# NumPad.net
KiCad netlist of a schematic drawn in EAGLE
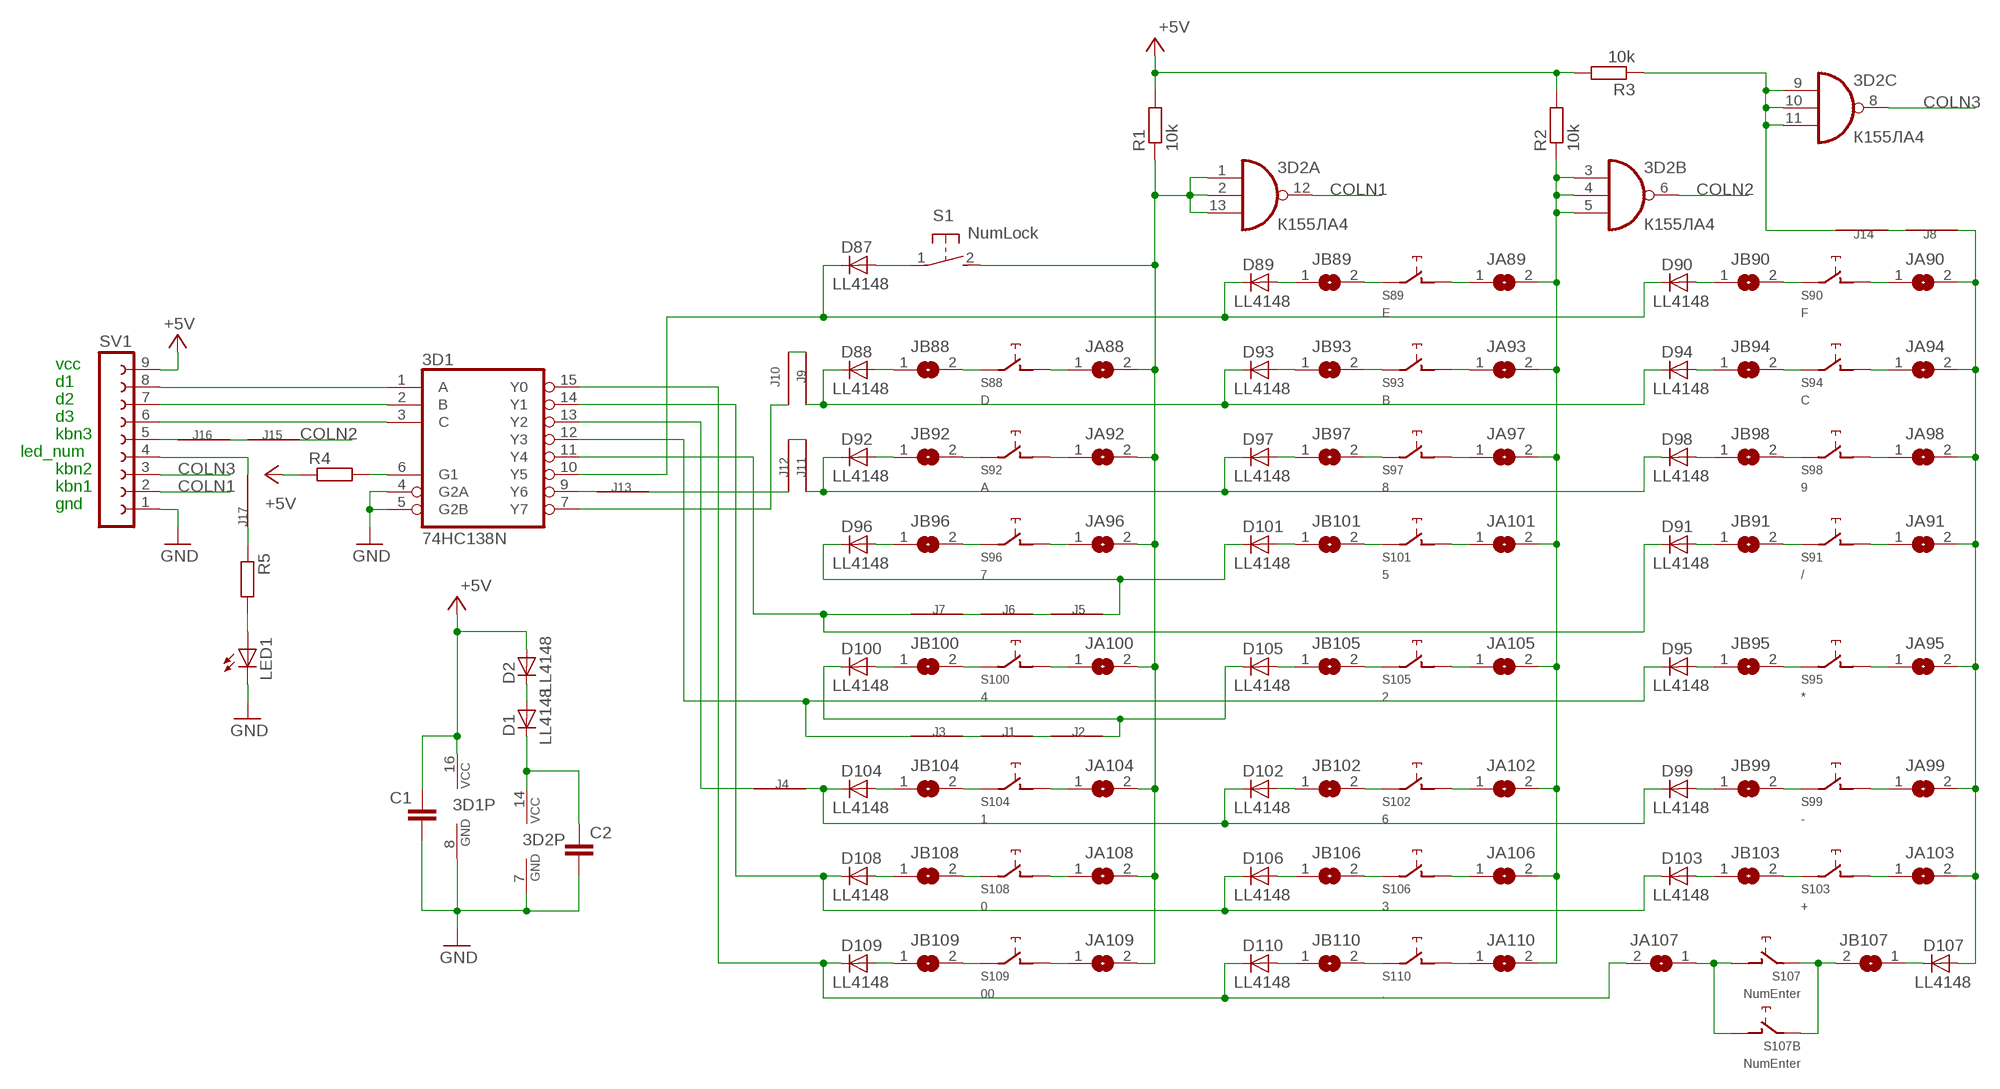
[diagram p0: schematic, sheet 1]

(export (version "E")
  (design (tool "Eeschema 10.0.6"))
  (components
    (comp (ref "3D1")
      (value "74HC138N")
      (footprint "eagle-import:DIL16")
      (libsource (lib "eagle-import") (part "74138NHC"))
    )
    (comp (ref "3D2")
      (value "К155ЛА4")
      (footprint "eagle-import:DIL14")
      (libsource (lib "eagle-import") (part "7410NHC"))
    )
    (comp (ref "C1")
      (value "C-EUC1206")
      (footprint "eagle-import:C1206")
      (libsource (lib "eagle-import") (part "C-EUC1206"))
    )
    (comp (ref "C2")
      (value "C-EUC1206")
      (footprint "eagle-import:C1206")
      (libsource (lib "eagle-import") (part "C-EUC1206"))
    )
    (comp (ref "D1")
      (value "LL4148")
      (footprint "eagle-import:SOD80C")
      (libsource (lib "eagle-import") (part "LL4148"))
    )
    (comp (ref "D2")
      (value "LL4148")
      (footprint "eagle-import:SOD80C")
      (libsource (lib "eagle-import") (part "LL4148"))
    )
    (comp (ref "D87")
      (value "LL4148")
      (footprint "eagle-import:SOD80C")
      (libsource (lib "eagle-import") (part "LL4148"))
    )
    (comp (ref "D88")
      (value "LL4148")
      (footprint "eagle-import:SOD80C")
      (libsource (lib "eagle-import") (part "LL4148"))
    )
    (comp (ref "D89")
      (value "LL4148")
      (footprint "eagle-import:SOD80C")
      (libsource (lib "eagle-import") (part "LL4148"))
    )
    (comp (ref "D90")
      (value "LL4148")
      (footprint "eagle-import:SOD80C")
      (libsource (lib "eagle-import") (part "LL4148"))
    )
    (comp (ref "D91")
      (value "LL4148")
      (footprint "eagle-import:SOD80C")
      (libsource (lib "eagle-import") (part "LL4148"))
    )
    (comp (ref "D92")
      (value "LL4148")
      (footprint "eagle-import:SOD80C")
      (libsource (lib "eagle-import") (part "LL4148"))
    )
    (comp (ref "D93")
      (value "LL4148")
      (footprint "eagle-import:SOD80C")
      (libsource (lib "eagle-import") (part "LL4148"))
    )
    (comp (ref "D94")
      (value "LL4148")
      (footprint "eagle-import:SOD80C")
      (libsource (lib "eagle-import") (part "LL4148"))
    )
    (comp (ref "D95")
      (value "LL4148")
      (footprint "eagle-import:SOD80C")
      (libsource (lib "eagle-import") (part "LL4148"))
    )
    (comp (ref "D96")
      (value "LL4148")
      (footprint "eagle-import:SOD80C")
      (libsource (lib "eagle-import") (part "LL4148"))
    )
    (comp (ref "D97")
      (value "LL4148")
      (footprint "eagle-import:SOD80C")
      (libsource (lib "eagle-import") (part "LL4148"))
    )
    (comp (ref "D98")
      (value "LL4148")
      (footprint "eagle-import:SOD80C")
      (libsource (lib "eagle-import") (part "LL4148"))
    )
    (comp (ref "D99")
      (value "LL4148")
      (footprint "eagle-import:SOD80C")
      (libsource (lib "eagle-import") (part "LL4148"))
    )
    (comp (ref "D100")
      (value "LL4148")
      (footprint "eagle-import:SOD80C")
      (libsource (lib "eagle-import") (part "LL4148"))
    )
    (comp (ref "D101")
      (value "LL4148")
      (footprint "eagle-import:SOD80C")
      (libsource (lib "eagle-import") (part "LL4148"))
    )
    (comp (ref "D102")
      (value "LL4148")
      (footprint "eagle-import:SOD80C")
      (libsource (lib "eagle-import") (part "LL4148"))
    )
    (comp (ref "D103")
      (value "LL4148")
      (footprint "eagle-import:SOD80C")
      (libsource (lib "eagle-import") (part "LL4148"))
    )
    (comp (ref "D104")
      (value "LL4148")
      (footprint "eagle-import:SOD80C")
      (libsource (lib "eagle-import") (part "LL4148"))
    )
    (comp (ref "D105")
      (value "LL4148")
      (footprint "eagle-import:SOD80C")
      (libsource (lib "eagle-import") (part "LL4148"))
    )
    (comp (ref "D106")
      (value "LL4148")
      (footprint "eagle-import:SOD80C")
      (libsource (lib "eagle-import") (part "LL4148"))
    )
    (comp (ref "D107")
      (value "LL4148")
      (footprint "eagle-import:SOD80C")
      (libsource (lib "eagle-import") (part "LL4148"))
    )
    (comp (ref "D108")
      (value "LL4148")
      (footprint "eagle-import:SOD80C")
      (libsource (lib "eagle-import") (part "LL4148"))
    )
    (comp (ref "D109")
      (value "LL4148")
      (footprint "eagle-import:SOD80C")
      (libsource (lib "eagle-import") (part "LL4148"))
    )
    (comp (ref "D110")
      (value "LL4148")
      (footprint "eagle-import:SOD80C")
      (libsource (lib "eagle-import") (part "LL4148"))
    )
    (comp (ref "J1")
      (value "J")
      (footprint "eagle-import:R1206W")
      (libsource (lib "eagle-import") (part "J"))
    )
    (comp (ref "J2")
      (value "J")
      (footprint "eagle-import:R1206W")
      (libsource (lib "eagle-import") (part "J"))
    )
    (comp (ref "J3")
      (value "J")
      (footprint "eagle-import:R1206W")
      (libsource (lib "eagle-import") (part "J"))
    )
    (comp (ref "J4")
      (value "J")
      (footprint "eagle-import:R1206W")
      (libsource (lib "eagle-import") (part "J"))
    )
    (comp (ref "J5")
      (value "J")
      (footprint "eagle-import:R1206W")
      (libsource (lib "eagle-import") (part "J"))
    )
    (comp (ref "J6")
      (value "J")
      (footprint "eagle-import:R1206W")
      (libsource (lib "eagle-import") (part "J"))
    )
    (comp (ref "J7")
      (value "J")
      (footprint "eagle-import:R1206W")
      (libsource (lib "eagle-import") (part "J"))
    )
    (comp (ref "J8")
      (value "J")
      (footprint "eagle-import:R1206W")
      (libsource (lib "eagle-import") (part "J"))
    )
    (comp (ref "J9")
      (value "J")
      (footprint "eagle-import:R1206W")
      (libsource (lib "eagle-import") (part "J"))
    )
    (comp (ref "J10")
      (value "J")
      (footprint "eagle-import:R1206W")
      (libsource (lib "eagle-import") (part "J"))
    )
    (comp (ref "J11")
      (value "J")
      (footprint "eagle-import:R1206W")
      (libsource (lib "eagle-import") (part "J"))
    )
    (comp (ref "J12")
      (value "J")
      (footprint "eagle-import:R1206W")
      (libsource (lib "eagle-import") (part "J"))
    )
    (comp (ref "J13")
      (value "J")
      (footprint "eagle-import:R1206W")
      (libsource (lib "eagle-import") (part "J"))
    )
    (comp (ref "J14")
      (value "J")
      (footprint "eagle-import:R1206W")
      (libsource (lib "eagle-import") (part "J"))
    )
    (comp (ref "J15")
      (value "J")
      (footprint "eagle-import:R1206W")
      (libsource (lib "eagle-import") (part "J"))
    )
    (comp (ref "J16")
      (value "J")
      (footprint "eagle-import:R1206W")
      (libsource (lib "eagle-import") (part "J"))
    )
    (comp (ref "J17")
      (value "J")
      (footprint "eagle-import:R1206W")
      (libsource (lib "eagle-import") (part "J"))
    )
    (comp (ref "JA88")
      (value "SJ")
      (footprint "eagle-import:SJ")
      (libsource (lib "eagle-import") (part "SJ"))
    )
    (comp (ref "JA89")
      (value "SJ")
      (footprint "eagle-import:SJ")
      (libsource (lib "eagle-import") (part "SJ"))
    )
    (comp (ref "JA90")
      (value "SJ")
      (footprint "eagle-import:SJ")
      (libsource (lib "eagle-import") (part "SJ"))
    )
    (comp (ref "JA91")
      (value "SJ")
      (footprint "eagle-import:SJ")
      (libsource (lib "eagle-import") (part "SJ"))
    )
    (comp (ref "JA92")
      (value "SJ")
      (footprint "eagle-import:SJ")
      (libsource (lib "eagle-import") (part "SJ"))
    )
    (comp (ref "JA93")
      (value "SJ")
      (footprint "eagle-import:SJ")
      (libsource (lib "eagle-import") (part "SJ"))
    )
    (comp (ref "JA94")
      (value "SJ")
      (footprint "eagle-import:SJ")
      (libsource (lib "eagle-import") (part "SJ"))
    )
    (comp (ref "JA95")
      (value "SJ")
      (footprint "eagle-import:SJ")
      (libsource (lib "eagle-import") (part "SJ"))
    )
    (comp (ref "JA96")
      (value "SJ")
      (footprint "eagle-import:SJ")
      (libsource (lib "eagle-import") (part "SJ"))
    )
    (comp (ref "JA97")
      (value "SJ")
      (footprint "eagle-import:SJ")
      (libsource (lib "eagle-import") (part "SJ"))
    )
    (comp (ref "JA98")
      (value "SJ")
      (footprint "eagle-import:SJ")
      (libsource (lib "eagle-import") (part "SJ"))
    )
    (comp (ref "JA99")
      (value "SJ")
      (footprint "eagle-import:SJ")
      (libsource (lib "eagle-import") (part "SJ"))
    )
    (comp (ref "JA100")
      (value "SJ")
      (footprint "eagle-import:SJ")
      (libsource (lib "eagle-import") (part "SJ"))
    )
    (comp (ref "JA101")
      (value "SJ")
      (footprint "eagle-import:SJ")
      (libsource (lib "eagle-import") (part "SJ"))
    )
    (comp (ref "JA102")
      (value "SJ")
      (footprint "eagle-import:SJ")
      (libsource (lib "eagle-import") (part "SJ"))
    )
    (comp (ref "JA103")
      (value "SJ")
      (footprint "eagle-import:SJ")
      (libsource (lib "eagle-import") (part "SJ"))
    )
    (comp (ref "JA104")
      (value "SJ")
      (footprint "eagle-import:SJ")
      (libsource (lib "eagle-import") (part "SJ"))
    )
    (comp (ref "JA105")
      (value "SJ")
      (footprint "eagle-import:SJ")
      (libsource (lib "eagle-import") (part "SJ"))
    )
    (comp (ref "JA106")
      (value "SJ")
      (footprint "eagle-import:SJ")
      (libsource (lib "eagle-import") (part "SJ"))
    )
    (comp (ref "JA107")
      (value "SJ")
      (footprint "eagle-import:SJ")
      (libsource (lib "eagle-import") (part "SJ"))
    )
    (comp (ref "JA108")
      (value "SJ")
      (footprint "eagle-import:SJ")
      (libsource (lib "eagle-import") (part "SJ"))
    )
    (comp (ref "JA109")
      (value "SJ")
      (footprint "eagle-import:SJ")
      (libsource (lib "eagle-import") (part "SJ"))
    )
    (comp (ref "JA110")
      (value "SJ")
      (footprint "eagle-import:SJ")
      (libsource (lib "eagle-import") (part "SJ"))
    )
    (comp (ref "JB88")
      (value "SJ")
      (footprint "eagle-import:SJ")
      (libsource (lib "eagle-import") (part "SJ"))
    )
    (comp (ref "JB89")
      (value "SJ")
      (footprint "eagle-import:SJ")
      (libsource (lib "eagle-import") (part "SJ"))
    )
    (comp (ref "JB90")
      (value "SJ")
      (footprint "eagle-import:SJ")
      (libsource (lib "eagle-import") (part "SJ"))
    )
    (comp (ref "JB91")
      (value "SJ")
      (footprint "eagle-import:SJ")
      (libsource (lib "eagle-import") (part "SJ"))
    )
    (comp (ref "JB92")
      (value "SJ")
      (footprint "eagle-import:SJ")
      (libsource (lib "eagle-import") (part "SJ"))
    )
    (comp (ref "JB93")
      (value "SJ")
      (footprint "eagle-import:SJ")
      (libsource (lib "eagle-import") (part "SJ"))
    )
    (comp (ref "JB94")
      (value "SJ")
      (footprint "eagle-import:SJ")
      (libsource (lib "eagle-import") (part "SJ"))
    )
    (comp (ref "JB95")
      (value "SJ")
      (footprint "eagle-import:SJ")
      (libsource (lib "eagle-import") (part "SJ"))
    )
    (comp (ref "JB96")
      (value "SJ")
      (footprint "eagle-import:SJ")
      (libsource (lib "eagle-import") (part "SJ"))
    )
    (comp (ref "JB97")
      (value "SJ")
      (footprint "eagle-import:SJ")
      (libsource (lib "eagle-import") (part "SJ"))
    )
    (comp (ref "JB98")
      (value "SJ")
      (footprint "eagle-import:SJ")
      (libsource (lib "eagle-import") (part "SJ"))
    )
    (comp (ref "JB99")
      (value "SJ")
      (footprint "eagle-import:SJ")
      (libsource (lib "eagle-import") (part "SJ"))
    )
    (comp (ref "JB100")
      (value "SJ")
      (footprint "eagle-import:SJ")
      (libsource (lib "eagle-import") (part "SJ"))
    )
    (comp (ref "JB101")
      (value "SJ")
      (footprint "eagle-import:SJ")
      (libsource (lib "eagle-import") (part "SJ"))
    )
    (comp (ref "JB102")
      (value "SJ")
      (footprint "eagle-import:SJ")
      (libsource (lib "eagle-import") (part "SJ"))
    )
    (comp (ref "JB103")
      (value "SJ")
      (footprint "eagle-import:SJ")
      (libsource (lib "eagle-import") (part "SJ"))
    )
    (comp (ref "JB104")
      (value "SJ")
      (footprint "eagle-import:SJ")
      (libsource (lib "eagle-import") (part "SJ"))
    )
    (comp (ref "JB105")
      (value "SJ")
      (footprint "eagle-import:SJ")
      (libsource (lib "eagle-import") (part "SJ"))
    )
    (comp (ref "JB106")
      (value "SJ")
      (footprint "eagle-import:SJ")
      (libsource (lib "eagle-import") (part "SJ"))
    )
    (comp (ref "JB107")
      (value "SJ")
      (footprint "eagle-import:SJ")
      (libsource (lib "eagle-import") (part "SJ"))
    )
    (comp (ref "JB108")
      (value "SJ")
      (footprint "eagle-import:SJ")
      (libsource (lib "eagle-import") (part "SJ"))
    )
    (comp (ref "JB109")
      (value "SJ")
      (footprint "eagle-import:SJ")
      (libsource (lib "eagle-import") (part "SJ"))
    )
    (comp (ref "JB110")
      (value "SJ")
      (footprint "eagle-import:SJ")
      (libsource (lib "eagle-import") (part "SJ"))
    )
    (comp (ref "LED1")
      (value "LED5MM")
      (footprint "eagle-import:LED5MM")
      (libsource (lib "eagle-import") (part "LED5MM"))
    )
    (comp (ref "R1")
      (value "10k")
      (footprint "eagle-import:R1206W")
      (libsource (lib "eagle-import") (part "R-EU_R1206W"))
    )
    (comp (ref "R2")
      (value "10k")
      (footprint "eagle-import:R1206W")
      (libsource (lib "eagle-import") (part "R-EU_R1206W"))
    )
    (comp (ref "R3")
      (value "10k")
      (footprint "eagle-import:R1206W")
      (libsource (lib "eagle-import") (part "R-EU_R1206W"))
    )
    (comp (ref "R4")
      (value "R-EU_R1206W")
      (footprint "eagle-import:R1206W")
      (libsource (lib "eagle-import") (part "R-EU_R1206W"))
    )
    (comp (ref "R5")
      (value "R-EU_R1206W")
      (footprint "eagle-import:R1206W")
      (libsource (lib "eagle-import") (part "R-EU_R1206W"))
    )
    (comp (ref "S1")
      (value "NumLock")
      (footprint "eagle-import:B3F-31XX")
      (fields (field (name "MPN") "B3F-3100"))
      (libsource (lib "eagle-import") (part "31-XX"))
    )
    (comp (ref "S88")
      (value "D")
      (footprint "eagle-import:CHERRY-MX-4P")
      (libsource (lib "eagle-import") (part "CHERRY-MX-4P"))
    )
    (comp (ref "S89")
      (value "E")
      (footprint "eagle-import:CHERRY-MX-4P")
      (libsource (lib "eagle-import") (part "CHERRY-MX-4P"))
    )
    (comp (ref "S90")
      (value "F")
      (footprint "eagle-import:CHERRY-MX-4P")
      (libsource (lib "eagle-import") (part "CHERRY-MX-4P"))
    )
    (comp (ref "S91")
      (value "/")
      (footprint "eagle-import:CHERRY-MX-4P")
      (libsource (lib "eagle-import") (part "CHERRY-MX-4P"))
    )
    (comp (ref "S92")
      (value "A")
      (footprint "eagle-import:CHERRY-MX-4P")
      (libsource (lib "eagle-import") (part "CHERRY-MX-4P"))
    )
    (comp (ref "S93")
      (value "B")
      (footprint "eagle-import:CHERRY-MX-4P")
      (libsource (lib "eagle-import") (part "CHERRY-MX-4P"))
    )
    (comp (ref "S94")
      (value "C")
      (footprint "eagle-import:CHERRY-MX-4P")
      (libsource (lib "eagle-import") (part "CHERRY-MX-4P"))
    )
    (comp (ref "S95")
      (value "*")
      (footprint "eagle-import:CHERRY-MX-4P")
      (libsource (lib "eagle-import") (part "CHERRY-MX-4P"))
    )
    (comp (ref "S96")
      (value "7")
      (footprint "eagle-import:CHERRY-MX-4P")
      (libsource (lib "eagle-import") (part "CHERRY-MX-4P"))
    )
    (comp (ref "S97")
      (value "8")
      (footprint "eagle-import:CHERRY-MX-4P")
      (libsource (lib "eagle-import") (part "CHERRY-MX-4P"))
    )
    (comp (ref "S98")
      (value "9")
      (footprint "eagle-import:CHERRY-MX-4P")
      (libsource (lib "eagle-import") (part "CHERRY-MX-4P"))
    )
    (comp (ref "S99")
      (value "-")
      (footprint "eagle-import:CHERRY-MX-4P")
      (libsource (lib "eagle-import") (part "CHERRY-MX-4P"))
    )
    (comp (ref "S100")
      (value "4")
      (footprint "eagle-import:CHERRY-MX-4P")
      (libsource (lib "eagle-import") (part "CHERRY-MX-4P"))
    )
    (comp (ref "S101")
      (value "5")
      (footprint "eagle-import:CHERRY-MX-4P")
      (libsource (lib "eagle-import") (part "CHERRY-MX-4P"))
    )
    (comp (ref "S102")
      (value "6")
      (footprint "eagle-import:CHERRY-MX-4P")
      (libsource (lib "eagle-import") (part "CHERRY-MX-4P"))
    )
    (comp (ref "S103")
      (value "+")
      (footprint "eagle-import:CHERRY-MX-4P")
      (libsource (lib "eagle-import") (part "CHERRY-MX-4P"))
    )
    (comp (ref "S104")
      (value "1")
      (footprint "eagle-import:CHERRY-MX-4P")
      (libsource (lib "eagle-import") (part "CHERRY-MX-4P"))
    )
    (comp (ref "S105")
      (value "2")
      (footprint "eagle-import:CHERRY-MX-4P")
      (libsource (lib "eagle-import") (part "CHERRY-MX-4P"))
    )
    (comp (ref "S106")
      (value "3")
      (footprint "eagle-import:CHERRY-MX-4P")
      (libsource (lib "eagle-import") (part "CHERRY-MX-4P"))
    )
    (comp (ref "S107")
      (value "NumEnter")
      (footprint "eagle-import:CHERRY-MX-4P")
      (libsource (lib "eagle-import") (part "CHERRY-MX-4P"))
    )
    (comp (ref "S107B")
      (value "NumEnter")
      (footprint "eagle-import:CHERRY-MX-4P")
      (libsource (lib "eagle-import") (part "CHERRY-MX-4P"))
    )
    (comp (ref "S108")
      (value "0")
      (footprint "eagle-import:CHERRY-MX-4P")
      (libsource (lib "eagle-import") (part "CHERRY-MX-4P"))
    )
    (comp (ref "S109")
      (value "00")
      (footprint "eagle-import:CHERRY-MX-4P")
      (libsource (lib "eagle-import") (part "CHERRY-MX-4P"))
    )
    (comp (ref "S110")
      (value ".")
      (footprint "eagle-import:CHERRY-MX-4P")
      (libsource (lib "eagle-import") (part "CHERRY-MX-4P"))
    )
    (comp (ref "SV1")
      (value "FE09-1")
      (footprint "eagle-import:FE09")
      (libsource (lib "eagle-import") (part "FE09-1"))
    )
  )
  (nets
    (net (code "1") (name "+5V") (class "Default")
      (node (ref "3D1") (pin "16") (pinfunction "VCC_16") (pintype "power_in"))
      (node (ref "C1") (pin "1") (pinfunction "1_1") (pintype "passive"))
      (node (ref "D2") (pin "A") (pinfunction "A_A") (pintype "passive"))
      (node (ref "R1") (pin "2") (pinfunction "2_2") (pintype "passive"))
      (node (ref "R2") (pin "2") (pinfunction "2_2") (pintype "passive"))
      (node (ref "R3") (pin "2") (pinfunction "2_2") (pintype "passive"))
      (node (ref "R4") (pin "1") (pinfunction "1_1") (pintype "passive"))
      (node (ref "SV1") (pin "9") (pinfunction "9_9") (pintype "passive"))
    )
    (net (code "2") (name "/COLN1") (class "Default")
      (node (ref "3D2") (pin "12") (pinfunction "O_12") (pintype "output"))
      (node (ref "SV1") (pin "2") (pinfunction "2_2") (pintype "passive"))
    )
    (net (code "3") (name "/COLN2") (class "Default")
      (node (ref "3D2") (pin "6") (pinfunction "O_6") (pintype "output"))
      (node (ref "J15") (pin "1") (pinfunction "P$1_1") (pintype "bidirectional"))
    )
    (net (code "4") (name "/COLN3") (class "Default")
      (node (ref "3D2") (pin "8") (pinfunction "O_8") (pintype "output"))
      (node (ref "SV1") (pin "3") (pinfunction "3_3") (pintype "passive"))
    )
    (net (code "5") (name "GND") (class "Default")
      (node (ref "3D1") (pin "4") (pinfunction "G2A_4") (pintype "input"))
      (node (ref "3D1") (pin "5") (pinfunction "G2B_5") (pintype "input"))
      (node (ref "3D1") (pin "8") (pinfunction "GND_8") (pintype "power_in"))
      (node (ref "3D2") (pin "7") (pinfunction "GND_7") (pintype "power_in"))
      (node (ref "C1") (pin "2") (pinfunction "2_2") (pintype "passive"))
      (node (ref "C2") (pin "2") (pinfunction "2_2") (pintype "passive"))
      (node (ref "LED1") (pin "K") (pinfunction "C_K") (pintype "passive"))
      (node (ref "SV1") (pin "1") (pinfunction "1_1") (pintype "passive"))
    )
    (net (code "6") (name "Net-(3D1A-A)") (class "Default")
      (node (ref "3D1") (pin "1") (pinfunction "A_1") (pintype "input"))
      (node (ref "SV1") (pin "8") (pinfunction "8_8") (pintype "passive"))
    )
    (net (code "7") (name "Net-(3D1A-B)") (class "Default")
      (node (ref "3D1") (pin "2") (pinfunction "B_2") (pintype "input"))
      (node (ref "SV1") (pin "7") (pinfunction "7_7") (pintype "passive"))
    )
    (net (code "8") (name "Net-(3D1A-C)") (class "Default")
      (node (ref "3D1") (pin "3") (pinfunction "C_3") (pintype "input"))
      (node (ref "SV1") (pin "6") (pinfunction "6_6") (pintype "passive"))
    )
    (net (code "9") (name "Net-(3D1A-G1)") (class "Default")
      (node (ref "3D1") (pin "6") (pinfunction "G1_6") (pintype "input"))
      (node (ref "R4") (pin "2") (pinfunction "2_2") (pintype "passive"))
    )
    (net (code "10") (name "Net-(3D1A-Y0)") (class "Default")
      (node (ref "3D1") (pin "15") (pinfunction "Y0_15") (pintype "output"))
      (node (ref "D109") (pin "C") (pinfunction "C_C") (pintype "passive"))
      (node (ref "D110") (pin "C") (pinfunction "C_C") (pintype "passive"))
      (node (ref "JA107") (pin "2") (pinfunction "2_2") (pintype "passive"))
    )
    (net (code "11") (name "Net-(3D1A-Y1)") (class "Default")
      (node (ref "3D1") (pin "14") (pinfunction "Y1_14") (pintype "output"))
      (node (ref "D103") (pin "C") (pinfunction "C_C") (pintype "passive"))
      (node (ref "D106") (pin "C") (pinfunction "C_C") (pintype "passive"))
      (node (ref "D108") (pin "C") (pinfunction "C_C") (pintype "passive"))
    )
    (net (code "12") (name "Net-(3D1A-Y2)") (class "Default")
      (node (ref "3D1") (pin "13") (pinfunction "Y2_13") (pintype "output"))
      (node (ref "J4") (pin "2") (pinfunction "P$2_2") (pintype "bidirectional"))
    )
    (net (code "13") (name "Net-(3D1A-Y3)") (class "Default")
      (node (ref "3D1") (pin "12") (pinfunction "Y3_12") (pintype "output"))
      (node (ref "D95") (pin "C") (pinfunction "C_C") (pintype "passive"))
      (node (ref "J3") (pin "2") (pinfunction "P$2_2") (pintype "bidirectional"))
    )
    (net (code "14") (name "Net-(3D1A-Y4)") (class "Default")
      (node (ref "3D1") (pin "11") (pinfunction "Y4_11") (pintype "output"))
      (node (ref "D91") (pin "C") (pinfunction "C_C") (pintype "passive"))
      (node (ref "J7") (pin "2") (pinfunction "P$2_2") (pintype "bidirectional"))
    )
    (net (code "15") (name "Net-(3D1A-Y5)") (class "Default")
      (node (ref "3D1") (pin "10") (pinfunction "Y5_10") (pintype "output"))
      (node (ref "D87") (pin "C") (pinfunction "C_C") (pintype "passive"))
      (node (ref "D89") (pin "C") (pinfunction "C_C") (pintype "passive"))
      (node (ref "D90") (pin "C") (pinfunction "C_C") (pintype "passive"))
    )
    (net (code "16") (name "Net-(3D1A-Y6)") (class "Default")
      (node (ref "3D1") (pin "9") (pinfunction "Y6_9") (pintype "output"))
      (node (ref "J13") (pin "2") (pinfunction "P$2_2") (pintype "bidirectional"))
    )
    (net (code "17") (name "Net-(3D1A-Y7)") (class "Default")
      (node (ref "3D1") (pin "7") (pinfunction "Y7_7") (pintype "output"))
      (node (ref "J10") (pin "1") (pinfunction "P$1_1") (pintype "bidirectional"))
    )
    (net (code "18") (name "Net-(3D2A-I0)") (class "Default")
      (node (ref "3D2") (pin "1") (pinfunction "I0_1") (pintype "input"))
      (node (ref "3D2") (pin "13") (pinfunction "I2_13") (pintype "input"))
      (node (ref "3D2") (pin "2") (pinfunction "I1_2") (pintype "input"))
      (node (ref "JA100") (pin "2") (pinfunction "2_2") (pintype "passive"))
      (node (ref "JA104") (pin "2") (pinfunction "2_2") (pintype "passive"))
      (node (ref "JA108") (pin "2") (pinfunction "2_2") (pintype "passive"))
      (node (ref "JA109") (pin "2") (pinfunction "2_2") (pintype "passive"))
      (node (ref "JA88") (pin "2") (pinfunction "2_2") (pintype "passive"))
      (node (ref "JA92") (pin "2") (pinfunction "2_2") (pintype "passive"))
      (node (ref "JA96") (pin "2") (pinfunction "2_2") (pintype "passive"))
      (node (ref "R1") (pin "1") (pinfunction "1_1") (pintype "passive"))
      (node (ref "S1") (pin "2") (pinfunction "S_2") (pintype "passive"))
    )
    (net (code "19") (name "Net-(3D2B-I0)") (class "Default")
      (node (ref "3D2") (pin "3") (pinfunction "I0_3") (pintype "input"))
      (node (ref "3D2") (pin "4") (pinfunction "I1_4") (pintype "input"))
      (node (ref "3D2") (pin "5") (pinfunction "I2_5") (pintype "input"))
      (node (ref "JA101") (pin "2") (pinfunction "2_2") (pintype "passive"))
      (node (ref "JA102") (pin "2") (pinfunction "2_2") (pintype "passive"))
      (node (ref "JA105") (pin "2") (pinfunction "2_2") (pintype "passive"))
      (node (ref "JA106") (pin "2") (pinfunction "2_2") (pintype "passive"))
      (node (ref "JA110") (pin "2") (pinfunction "2_2") (pintype "passive"))
      (node (ref "JA89") (pin "2") (pinfunction "2_2") (pintype "passive"))
      (node (ref "JA93") (pin "2") (pinfunction "2_2") (pintype "passive"))
      (node (ref "JA97") (pin "2") (pinfunction "2_2") (pintype "passive"))
      (node (ref "R2") (pin "1") (pinfunction "1_1") (pintype "passive"))
    )
    (net (code "20") (name "Net-(3D2C-I0)") (class "Default")
      (node (ref "3D2") (pin "10") (pinfunction "I1_10") (pintype "input"))
      (node (ref "3D2") (pin "11") (pinfunction "I2_11") (pintype "input"))
      (node (ref "3D2") (pin "9") (pinfunction "I0_9") (pintype "input"))
      (node (ref "J14") (pin "1") (pinfunction "P$1_1") (pintype "bidirectional"))
      (node (ref "R3") (pin "1") (pinfunction "1_1") (pintype "passive"))
    )
    (net (code "21") (name "Net-(3D2D-VCC)") (class "Default")
      (node (ref "3D2") (pin "14") (pinfunction "VCC_14") (pintype "power_in"))
      (node (ref "C2") (pin "1") (pinfunction "1_1") (pintype "passive"))
      (node (ref "D1") (pin "C") (pinfunction "C_C") (pintype "passive"))
    )
    (net (code "22") (name "Net-(D1-PadA)") (class "Default")
      (node (ref "D1") (pin "A") (pinfunction "A_A") (pintype "passive"))
      (node (ref "D2") (pin "C") (pinfunction "C_C") (pintype "passive"))
    )
    (net (code "23") (name "Net-(D88-PadA)") (class "Default")
      (node (ref "D88") (pin "A") (pinfunction "A_A") (pintype "passive"))
      (node (ref "JB88") (pin "1") (pinfunction "1_1") (pintype "passive"))
    )
    (net (code "24") (name "Net-(D89-PadA)") (class "Default")
      (node (ref "D89") (pin "A") (pinfunction "A_A") (pintype "passive"))
      (node (ref "JB89") (pin "1") (pinfunction "1_1") (pintype "passive"))
    )
    (net (code "25") (name "Net-(D90-PadA)") (class "Default")
      (node (ref "D90") (pin "A") (pinfunction "A_A") (pintype "passive"))
      (node (ref "JB90") (pin "1") (pinfunction "1_1") (pintype "passive"))
    )
    (net (code "26") (name "Net-(D91-PadA)") (class "Default")
      (node (ref "D91") (pin "A") (pinfunction "A_A") (pintype "passive"))
      (node (ref "JB91") (pin "1") (pinfunction "1_1") (pintype "passive"))
    )
    (net (code "27") (name "Net-(D92-PadA)") (class "Default")
      (node (ref "D92") (pin "A") (pinfunction "A_A") (pintype "passive"))
      (node (ref "JB92") (pin "1") (pinfunction "1_1") (pintype "passive"))
    )
    (net (code "28") (name "Net-(D93-PadA)") (class "Default")
      (node (ref "D93") (pin "A") (pinfunction "A_A") (pintype "passive"))
      (node (ref "JB93") (pin "1") (pinfunction "1_1") (pintype "passive"))
    )
    (net (code "29") (name "Net-(D94-PadA)") (class "Default")
      (node (ref "D94") (pin "A") (pinfunction "A_A") (pintype "passive"))
      (node (ref "JB94") (pin "1") (pinfunction "1_1") (pintype "passive"))
    )
    (net (code "30") (name "Net-(D95-PadA)") (class "Default")
      (node (ref "D95") (pin "A") (pinfunction "A_A") (pintype "passive"))
      (node (ref "JB95") (pin "1") (pinfunction "1_1") (pintype "passive"))
    )
    (net (code "31") (name "Net-(D96-PadA)") (class "Default")
      (node (ref "D96") (pin "A") (pinfunction "A_A") (pintype "passive"))
      (node (ref "JB96") (pin "1") (pinfunction "1_1") (pintype "passive"))
    )
    (net (code "32") (name "Net-(D97-PadA)") (class "Default")
      (node (ref "D97") (pin "A") (pinfunction "A_A") (pintype "passive"))
      (node (ref "JB97") (pin "1") (pinfunction "1_1") (pintype "passive"))
    )
    (net (code "33") (name "Net-(D98-PadA)") (class "Default")
      (node (ref "D98") (pin "A") (pinfunction "A_A") (pintype "passive"))
      (node (ref "JB98") (pin "1") (pinfunction "1_1") (pintype "passive"))
    )
    (net (code "34") (name "Net-(D99-PadA)") (class "Default")
      (node (ref "D99") (pin "A") (pinfunction "A_A") (pintype "passive"))
      (node (ref "JB99") (pin "1") (pinfunction "1_1") (pintype "passive"))
    )
    (net (code "35") (name "Net-(D100-PadA)") (class "Default")
      (node (ref "D100") (pin "A") (pinfunction "A_A") (pintype "passive"))
      (node (ref "JB100") (pin "1") (pinfunction "1_1") (pintype "passive"))
    )
    (net (code "36") (name "Net-(D101-PadA)") (class "Default")
      (node (ref "D101") (pin "A") (pinfunction "A_A") (pintype "passive"))
      (node (ref "JB101") (pin "1") (pinfunction "1_1") (pintype "passive"))
    )
    (net (code "37") (name "Net-(D102-PadA)") (class "Default")
      (node (ref "D102") (pin "A") (pinfunction "A_A") (pintype "passive"))
      (node (ref "JB102") (pin "1") (pinfunction "1_1") (pintype "passive"))
    )
    (net (code "38") (name "Net-(D103-PadA)") (class "Default")
      (node (ref "D103") (pin "A") (pinfunction "A_A") (pintype "passive"))
      (node (ref "JB103") (pin "1") (pinfunction "1_1") (pintype "passive"))
    )
    (net (code "39") (name "Net-(D104-PadA)") (class "Default")
      (node (ref "D104") (pin "A") (pinfunction "A_A") (pintype "passive"))
      (node (ref "JB104") (pin "1") (pinfunction "1_1") (pintype "passive"))
    )
    (net (code "40") (name "Net-(D105-PadA)") (class "Default")
      (node (ref "D105") (pin "A") (pinfunction "A_A") (pintype "passive"))
      (node (ref "JB105") (pin "1") (pinfunction "1_1") (pintype "passive"))
    )
    (net (code "41") (name "Net-(D106-PadA)") (class "Default")
      (node (ref "D106") (pin "A") (pinfunction "A_A") (pintype "passive"))
      (node (ref "JB106") (pin "1") (pinfunction "1_1") (pintype "passive"))
    )
    (net (code "42") (name "Net-(D107-PadC)") (class "Default")
      (node (ref "D107") (pin "C") (pinfunction "C_C") (pintype "passive"))
      (node (ref "JB107") (pin "1") (pinfunction "1_1") (pintype "passive"))
    )
    (net (code "43") (name "Net-(D108-PadA)") (class "Default")
      (node (ref "D108") (pin "A") (pinfunction "A_A") (pintype "passive"))
      (node (ref "JB108") (pin "1") (pinfunction "1_1") (pintype "passive"))
    )
    (net (code "44") (name "Net-(D109-PadA)") (class "Default")
      (node (ref "D109") (pin "A") (pinfunction "A_A") (pintype "passive"))
      (node (ref "JB109") (pin "1") (pinfunction "1_1") (pintype "passive"))
    )
    (net (code "45") (name "Net-(D110-PadA)") (class "Default")
      (node (ref "D110") (pin "A") (pinfunction "A_A") (pintype "passive"))
      (node (ref "JB110") (pin "1") (pinfunction "1_1") (pintype "passive"))
    )
    (net (code "46") (name "Net-(J1-P$1)") (class "Default")
      (node (ref "J1") (pin "1") (pinfunction "P$1_1") (pintype "bidirectional"))
      (node (ref "J2") (pin "2") (pinfunction "P$2_2") (pintype "bidirectional"))
    )
    (net (code "47") (name "Net-(J1-P$2)") (class "Default")
      (node (ref "J1") (pin "2") (pinfunction "P$2_2") (pintype "bidirectional"))
      (node (ref "J3") (pin "1") (pinfunction "P$1_1") (pintype "bidirectional"))
    )
    (net (code "48") (name "Net-(J2-P$1)") (class "Default")
      (node (ref "D100") (pin "C") (pinfunction "C_C") (pintype "passive"))
      (node (ref "D105") (pin "C") (pinfunction "C_C") (pintype "passive"))
      (node (ref "J2") (pin "1") (pinfunction "P$1_1") (pintype "bidirectional"))
    )
    (net (code "49") (name "Net-(J4-P$1)") (class "Default")
      (node (ref "D102") (pin "C") (pinfunction "C_C") (pintype "passive"))
      (node (ref "D104") (pin "C") (pinfunction "C_C") (pintype "passive"))
      (node (ref "D99") (pin "C") (pinfunction "C_C") (pintype "passive"))
      (node (ref "J4") (pin "1") (pinfunction "P$1_1") (pintype "bidirectional"))
    )
    (net (code "50") (name "Net-(J5-P$1)") (class "Default")
      (node (ref "D101") (pin "C") (pinfunction "C_C") (pintype "passive"))
      (node (ref "D96") (pin "C") (pinfunction "C_C") (pintype "passive"))
      (node (ref "J5") (pin "1") (pinfunction "P$1_1") (pintype "bidirectional"))
    )
    (net (code "51") (name "Net-(J5-P$2)") (class "Default")
      (node (ref "J5") (pin "2") (pinfunction "P$2_2") (pintype "bidirectional"))
      (node (ref "J6") (pin "1") (pinfunction "P$1_1") (pintype "bidirectional"))
    )
    (net (code "52") (name "Net-(J6-P$2)") (class "Default")
      (node (ref "J6") (pin "2") (pinfunction "P$2_2") (pintype "bidirectional"))
      (node (ref "J7") (pin "1") (pinfunction "P$1_1") (pintype "bidirectional"))
    )
    (net (code "53") (name "Net-(J8-P$2)") (class "Default")
      (node (ref "D107") (pin "A") (pinfunction "A_A") (pintype "passive"))
      (node (ref "J8") (pin "2") (pinfunction "P$2_2") (pintype "bidirectional"))
      (node (ref "JA103") (pin "2") (pinfunction "2_2") (pintype "passive"))
      (node (ref "JA90") (pin "2") (pinfunction "2_2") (pintype "passive"))
      (node (ref "JA91") (pin "2") (pinfunction "2_2") (pintype "passive"))
      (node (ref "JA94") (pin "2") (pinfunction "2_2") (pintype "passive"))
      (node (ref "JA95") (pin "2") (pinfunction "2_2") (pintype "passive"))
      (node (ref "JA98") (pin "2") (pinfunction "2_2") (pintype "passive"))
      (node (ref "JA99") (pin "2") (pinfunction "2_2") (pintype "passive"))
    )
    (net (code "54") (name "Net-(J9-P$2)") (class "Default")
      (node (ref "D88") (pin "C") (pinfunction "C_C") (pintype "passive"))
      (node (ref "D93") (pin "C") (pinfunction "C_C") (pintype "passive"))
      (node (ref "D94") (pin "C") (pinfunction "C_C") (pintype "passive"))
      (node (ref "J9") (pin "2") (pinfunction "P$2_2") (pintype "bidirectional"))
    )
    (net (code "55") (name "Net-(J10-P$2)") (class "Default")
      (node (ref "J10") (pin "2") (pinfunction "P$2_2") (pintype "bidirectional"))
      (node (ref "J9") (pin "1") (pinfunction "P$1_1") (pintype "bidirectional"))
    )
    (net (code "56") (name "Net-(J11-P$1)") (class "Default")
      (node (ref "J11") (pin "1") (pinfunction "P$1_1") (pintype "bidirectional"))
      (node (ref "J12") (pin "1") (pinfunction "P$1_1") (pintype "bidirectional"))
    )
    (net (code "57") (name "Net-(J11-P$2)") (class "Default")
      (node (ref "D92") (pin "C") (pinfunction "C_C") (pintype "passive"))
      (node (ref "D97") (pin "C") (pinfunction "C_C") (pintype "passive"))
      (node (ref "D98") (pin "C") (pinfunction "C_C") (pintype "passive"))
      (node (ref "J11") (pin "2") (pinfunction "P$2_2") (pintype "bidirectional"))
    )
    (net (code "58") (name "Net-(J12-P$2)") (class "Default")
      (node (ref "J12") (pin "2") (pinfunction "P$2_2") (pintype "bidirectional"))
      (node (ref "J13") (pin "1") (pinfunction "P$1_1") (pintype "bidirectional"))
    )
    (net (code "59") (name "Net-(J14-P$2)") (class "Default")
      (node (ref "J14") (pin "2") (pinfunction "P$2_2") (pintype "bidirectional"))
      (node (ref "J8") (pin "1") (pinfunction "P$1_1") (pintype "bidirectional"))
    )
    (net (code "60") (name "Net-(J15-P$2)") (class "Default")
      (node (ref "J15") (pin "2") (pinfunction "P$2_2") (pintype "bidirectional"))
      (node (ref "J16") (pin "1") (pinfunction "P$1_1") (pintype "bidirectional"))
    )
    (net (code "61") (name "Net-(J16-P$2)") (class "Default")
      (node (ref "J16") (pin "2") (pinfunction "P$2_2") (pintype "bidirectional"))
      (node (ref "SV1") (pin "5") (pinfunction "5_5") (pintype "passive"))
    )
    (net (code "62") (name "Net-(J17-P$1)") (class "Default")
      (node (ref "J17") (pin "1") (pinfunction "P$1_1") (pintype "bidirectional"))
      (node (ref "R5") (pin "1") (pinfunction "1_1") (pintype "passive"))
    )
    (net (code "63") (name "Net-(J17-P$2)") (class "Default")
      (node (ref "J17") (pin "2") (pinfunction "P$2_2") (pintype "bidirectional"))
      (node (ref "SV1") (pin "4") (pinfunction "4_4") (pintype "passive"))
    )
    (net (code "64") (name "Net-(LED1-PadA)") (class "Default")
      (node (ref "LED1") (pin "A") (pinfunction "A_A") (pintype "passive"))
      (node (ref "R5") (pin "2") (pinfunction "2_2") (pintype "passive"))
    )
    (net (code "65") (name "Net-(S1-P)") (class "Default")
      (node (ref "D87") (pin "A") (pinfunction "A_A") (pintype "passive"))
      (node (ref "S1") (pin "1") (pinfunction "P_1") (pintype "passive"))
    )
    (net (code "66") (name "Net-(S88A-PIN-1)") (class "Default")
      (node (ref "JB88") (pin "2") (pinfunction "2_2") (pintype "passive"))
      (node (ref "S88") (pin "SW1") (pinfunction "PIN-1_SW1") (pintype "passive"))
    )
    (net (code "67") (name "Net-(S88A-PIN-2)") (class "Default")
      (node (ref "JA88") (pin "1") (pinfunction "1_1") (pintype "passive"))
      (node (ref "S88") (pin "SW2") (pinfunction "PIN-2_SW2") (pintype "passive"))
    )
    (net (code "68") (name "Net-(S89A-PIN-1)") (class "Default")
      (node (ref "JB89") (pin "2") (pinfunction "2_2") (pintype "passive"))
      (node (ref "S89") (pin "SW1") (pinfunction "PIN-1_SW1") (pintype "passive"))
    )
    (net (code "69") (name "Net-(S89A-PIN-2)") (class "Default")
      (node (ref "JA89") (pin "1") (pinfunction "1_1") (pintype "passive"))
      (node (ref "S89") (pin "SW2") (pinfunction "PIN-2_SW2") (pintype "passive"))
    )
    (net (code "70") (name "Net-(S90A-PIN-1)") (class "Default")
      (node (ref "JB90") (pin "2") (pinfunction "2_2") (pintype "passive"))
      (node (ref "S90") (pin "SW1") (pinfunction "PIN-1_SW1") (pintype "passive"))
    )
    (net (code "71") (name "Net-(S90A-PIN-2)") (class "Default")
      (node (ref "JA90") (pin "1") (pinfunction "1_1") (pintype "passive"))
      (node (ref "S90") (pin "SW2") (pinfunction "PIN-2_SW2") (pintype "passive"))
    )
    (net (code "72") (name "Net-(S91A-PIN-1)") (class "Default")
      (node (ref "JB91") (pin "2") (pinfunction "2_2") (pintype "passive"))
      (node (ref "S91") (pin "SW1") (pinfunction "PIN-1_SW1") (pintype "passive"))
    )
    (net (code "73") (name "Net-(S91A-PIN-2)") (class "Default")
      (node (ref "JA91") (pin "1") (pinfunction "1_1") (pintype "passive"))
      (node (ref "S91") (pin "SW2") (pinfunction "PIN-2_SW2") (pintype "passive"))
    )
    (net (code "74") (name "Net-(S92A-PIN-1)") (class "Default")
      (node (ref "JB92") (pin "2") (pinfunction "2_2") (pintype "passive"))
      (node (ref "S92") (pin "SW1") (pinfunction "PIN-1_SW1") (pintype "passive"))
    )
    (net (code "75") (name "Net-(S92A-PIN-2)") (class "Default")
      (node (ref "JA92") (pin "1") (pinfunction "1_1") (pintype "passive"))
      (node (ref "S92") (pin "SW2") (pinfunction "PIN-2_SW2") (pintype "passive"))
    )
    (net (code "76") (name "Net-(S93A-PIN-1)") (class "Default")
      (node (ref "JB93") (pin "2") (pinfunction "2_2") (pintype "passive"))
      (node (ref "S93") (pin "SW1") (pinfunction "PIN-1_SW1") (pintype "passive"))
    )
    (net (code "77") (name "Net-(S93A-PIN-2)") (class "Default")
      (node (ref "JA93") (pin "1") (pinfunction "1_1") (pintype "passive"))
      (node (ref "S93") (pin "SW2") (pinfunction "PIN-2_SW2") (pintype "passive"))
    )
    (net (code "78") (name "Net-(S94A-PIN-1)") (class "Default")
      (node (ref "JB94") (pin "2") (pinfunction "2_2") (pintype "passive"))
      (node (ref "S94") (pin "SW1") (pinfunction "PIN-1_SW1") (pintype "passive"))
    )
    (net (code "79") (name "Net-(S94A-PIN-2)") (class "Default")
      (node (ref "JA94") (pin "1") (pinfunction "1_1") (pintype "passive"))
      (node (ref "S94") (pin "SW2") (pinfunction "PIN-2_SW2") (pintype "passive"))
    )
    (net (code "80") (name "Net-(S95A-PIN-1)") (class "Default")
      (node (ref "JB95") (pin "2") (pinfunction "2_2") (pintype "passive"))
      (node (ref "S95") (pin "SW1") (pinfunction "PIN-1_SW1") (pintype "passive"))
    )
    (net (code "81") (name "Net-(S95A-PIN-2)") (class "Default")
      (node (ref "JA95") (pin "1") (pinfunction "1_1") (pintype "passive"))
      (node (ref "S95") (pin "SW2") (pinfunction "PIN-2_SW2") (pintype "passive"))
    )
    (net (code "82") (name "Net-(S96A-PIN-1)") (class "Default")
      (node (ref "JB96") (pin "2") (pinfunction "2_2") (pintype "passive"))
      (node (ref "S96") (pin "SW1") (pinfunction "PIN-1_SW1") (pintype "passive"))
    )
    (net (code "83") (name "Net-(S96A-PIN-2)") (class "Default")
      (node (ref "JA96") (pin "1") (pinfunction "1_1") (pintype "passive"))
      (node (ref "S96") (pin "SW2") (pinfunction "PIN-2_SW2") (pintype "passive"))
    )
    (net (code "84") (name "Net-(S97A-PIN-1)") (class "Default")
      (node (ref "JB97") (pin "2") (pinfunction "2_2") (pintype "passive"))
      (node (ref "S97") (pin "SW1") (pinfunction "PIN-1_SW1") (pintype "passive"))
    )
    (net (code "85") (name "Net-(S97A-PIN-2)") (class "Default")
      (node (ref "JA97") (pin "1") (pinfunction "1_1") (pintype "passive"))
      (node (ref "S97") (pin "SW2") (pinfunction "PIN-2_SW2") (pintype "passive"))
    )
    (net (code "86") (name "Net-(S98A-PIN-1)") (class "Default")
      (node (ref "JB98") (pin "2") (pinfunction "2_2") (pintype "passive"))
      (node (ref "S98") (pin "SW1") (pinfunction "PIN-1_SW1") (pintype "passive"))
    )
    (net (code "87") (name "Net-(S98A-PIN-2)") (class "Default")
      (node (ref "JA98") (pin "1") (pinfunction "1_1") (pintype "passive"))
      (node (ref "S98") (pin "SW2") (pinfunction "PIN-2_SW2") (pintype "passive"))
    )
    (net (code "88") (name "Net-(S99A-PIN-1)") (class "Default")
      (node (ref "JB99") (pin "2") (pinfunction "2_2") (pintype "passive"))
      (node (ref "S99") (pin "SW1") (pinfunction "PIN-1_SW1") (pintype "passive"))
    )
    (net (code "89") (name "Net-(S99A-PIN-2)") (class "Default")
      (node (ref "JA99") (pin "1") (pinfunction "1_1") (pintype "passive"))
      (node (ref "S99") (pin "SW2") (pinfunction "PIN-2_SW2") (pintype "passive"))
    )
    (net (code "90") (name "Net-(S100A-PIN-1)") (class "Default")
      (node (ref "JB100") (pin "2") (pinfunction "2_2") (pintype "passive"))
      (node (ref "S100") (pin "SW1") (pinfunction "PIN-1_SW1") (pintype "passive"))
    )
    (net (code "91") (name "Net-(S100A-PIN-2)") (class "Default")
      (node (ref "JA100") (pin "1") (pinfunction "1_1") (pintype "passive"))
      (node (ref "S100") (pin "SW2") (pinfunction "PIN-2_SW2") (pintype "passive"))
    )
    (net (code "92") (name "Net-(S101A-PIN-1)") (class "Default")
      (node (ref "JB101") (pin "2") (pinfunction "2_2") (pintype "passive"))
      (node (ref "S101") (pin "SW1") (pinfunction "PIN-1_SW1") (pintype "passive"))
    )
    (net (code "93") (name "Net-(S101A-PIN-2)") (class "Default")
      (node (ref "JA101") (pin "1") (pinfunction "1_1") (pintype "passive"))
      (node (ref "S101") (pin "SW2") (pinfunction "PIN-2_SW2") (pintype "passive"))
    )
    (net (code "94") (name "Net-(S102A-PIN-1)") (class "Default")
      (node (ref "JB102") (pin "2") (pinfunction "2_2") (pintype "passive"))
      (node (ref "S102") (pin "SW1") (pinfunction "PIN-1_SW1") (pintype "passive"))
    )
    (net (code "95") (name "Net-(S102A-PIN-2)") (class "Default")
      (node (ref "JA102") (pin "1") (pinfunction "1_1") (pintype "passive"))
      (node (ref "S102") (pin "SW2") (pinfunction "PIN-2_SW2") (pintype "passive"))
    )
    (net (code "96") (name "Net-(S103A-PIN-1)") (class "Default")
      (node (ref "JB103") (pin "2") (pinfunction "2_2") (pintype "passive"))
      (node (ref "S103") (pin "SW1") (pinfunction "PIN-1_SW1") (pintype "passive"))
    )
    (net (code "97") (name "Net-(S103A-PIN-2)") (class "Default")
      (node (ref "JA103") (pin "1") (pinfunction "1_1") (pintype "passive"))
      (node (ref "S103") (pin "SW2") (pinfunction "PIN-2_SW2") (pintype "passive"))
    )
    (net (code "98") (name "Net-(S104A-PIN-1)") (class "Default")
      (node (ref "JB104") (pin "2") (pinfunction "2_2") (pintype "passive"))
      (node (ref "S104") (pin "SW1") (pinfunction "PIN-1_SW1") (pintype "passive"))
    )
    (net (code "99") (name "Net-(S104A-PIN-2)") (class "Default")
      (node (ref "JA104") (pin "1") (pinfunction "1_1") (pintype "passive"))
      (node (ref "S104") (pin "SW2") (pinfunction "PIN-2_SW2") (pintype "passive"))
    )
    (net (code "100") (name "Net-(S105A-PIN-1)") (class "Default")
      (node (ref "JB105") (pin "2") (pinfunction "2_2") (pintype "passive"))
      (node (ref "S105") (pin "SW1") (pinfunction "PIN-1_SW1") (pintype "passive"))
    )
    (net (code "101") (name "Net-(S105A-PIN-2)") (class "Default")
      (node (ref "JA105") (pin "1") (pinfunction "1_1") (pintype "passive"))
      (node (ref "S105") (pin "SW2") (pinfunction "PIN-2_SW2") (pintype "passive"))
    )
    (net (code "102") (name "Net-(S106A-PIN-1)") (class "Default")
      (node (ref "JB106") (pin "2") (pinfunction "2_2") (pintype "passive"))
      (node (ref "S106") (pin "SW1") (pinfunction "PIN-1_SW1") (pintype "passive"))
    )
    (net (code "103") (name "Net-(S106A-PIN-2)") (class "Default")
      (node (ref "JA106") (pin "1") (pinfunction "1_1") (pintype "passive"))
      (node (ref "S106") (pin "SW2") (pinfunction "PIN-2_SW2") (pintype "passive"))
    )
    (net (code "104") (name "Net-(S107A-PIN-1)") (class "Default")
      (node (ref "JB107") (pin "2") (pinfunction "2_2") (pintype "passive"))
      (node (ref "S107") (pin "SW1") (pinfunction "PIN-1_SW1") (pintype "passive"))
      (node (ref "S107B") (pin "SW1") (pinfunction "PIN-1_SW1") (pintype "passive"))
    )
    (net (code "105") (name "Net-(S107A-PIN-2)") (class "Default")
      (node (ref "JA107") (pin "1") (pinfunction "1_1") (pintype "passive"))
      (node (ref "S107") (pin "SW2") (pinfunction "PIN-2_SW2") (pintype "passive"))
      (node (ref "S107B") (pin "SW2") (pinfunction "PIN-2_SW2") (pintype "passive"))
    )
    (net (code "106") (name "Net-(S108A-PIN-1)") (class "Default")
      (node (ref "JB108") (pin "2") (pinfunction "2_2") (pintype "passive"))
      (node (ref "S108") (pin "SW1") (pinfunction "PIN-1_SW1") (pintype "passive"))
    )
    (net (code "107") (name "Net-(S108A-PIN-2)") (class "Default")
      (node (ref "JA108") (pin "1") (pinfunction "1_1") (pintype "passive"))
      (node (ref "S108") (pin "SW2") (pinfunction "PIN-2_SW2") (pintype "passive"))
    )
    (net (code "108") (name "Net-(S109A-PIN-1)") (class "Default")
      (node (ref "JB109") (pin "2") (pinfunction "2_2") (pintype "passive"))
      (node (ref "S109") (pin "SW1") (pinfunction "PIN-1_SW1") (pintype "passive"))
    )
    (net (code "109") (name "Net-(S109A-PIN-2)") (class "Default")
      (node (ref "JA109") (pin "1") (pinfunction "1_1") (pintype "passive"))
      (node (ref "S109") (pin "SW2") (pinfunction "PIN-2_SW2") (pintype "passive"))
    )
    (net (code "110") (name "Net-(S110A-PIN-1)") (class "Default")
      (node (ref "JB110") (pin "2") (pinfunction "2_2") (pintype "passive"))
      (node (ref "S110") (pin "SW1") (pinfunction "PIN-1_SW1") (pintype "passive"))
    )
    (net (code "111") (name "Net-(S110A-PIN-2)") (class "Default")
      (node (ref "JA110") (pin "1") (pinfunction "1_1") (pintype "passive"))
      (node (ref "S110") (pin "SW2") (pinfunction "PIN-2_SW2") (pintype "passive"))
    )
  )
)
